# calculator3.net
KiCad netlist of a schematic drawn in EAGLE
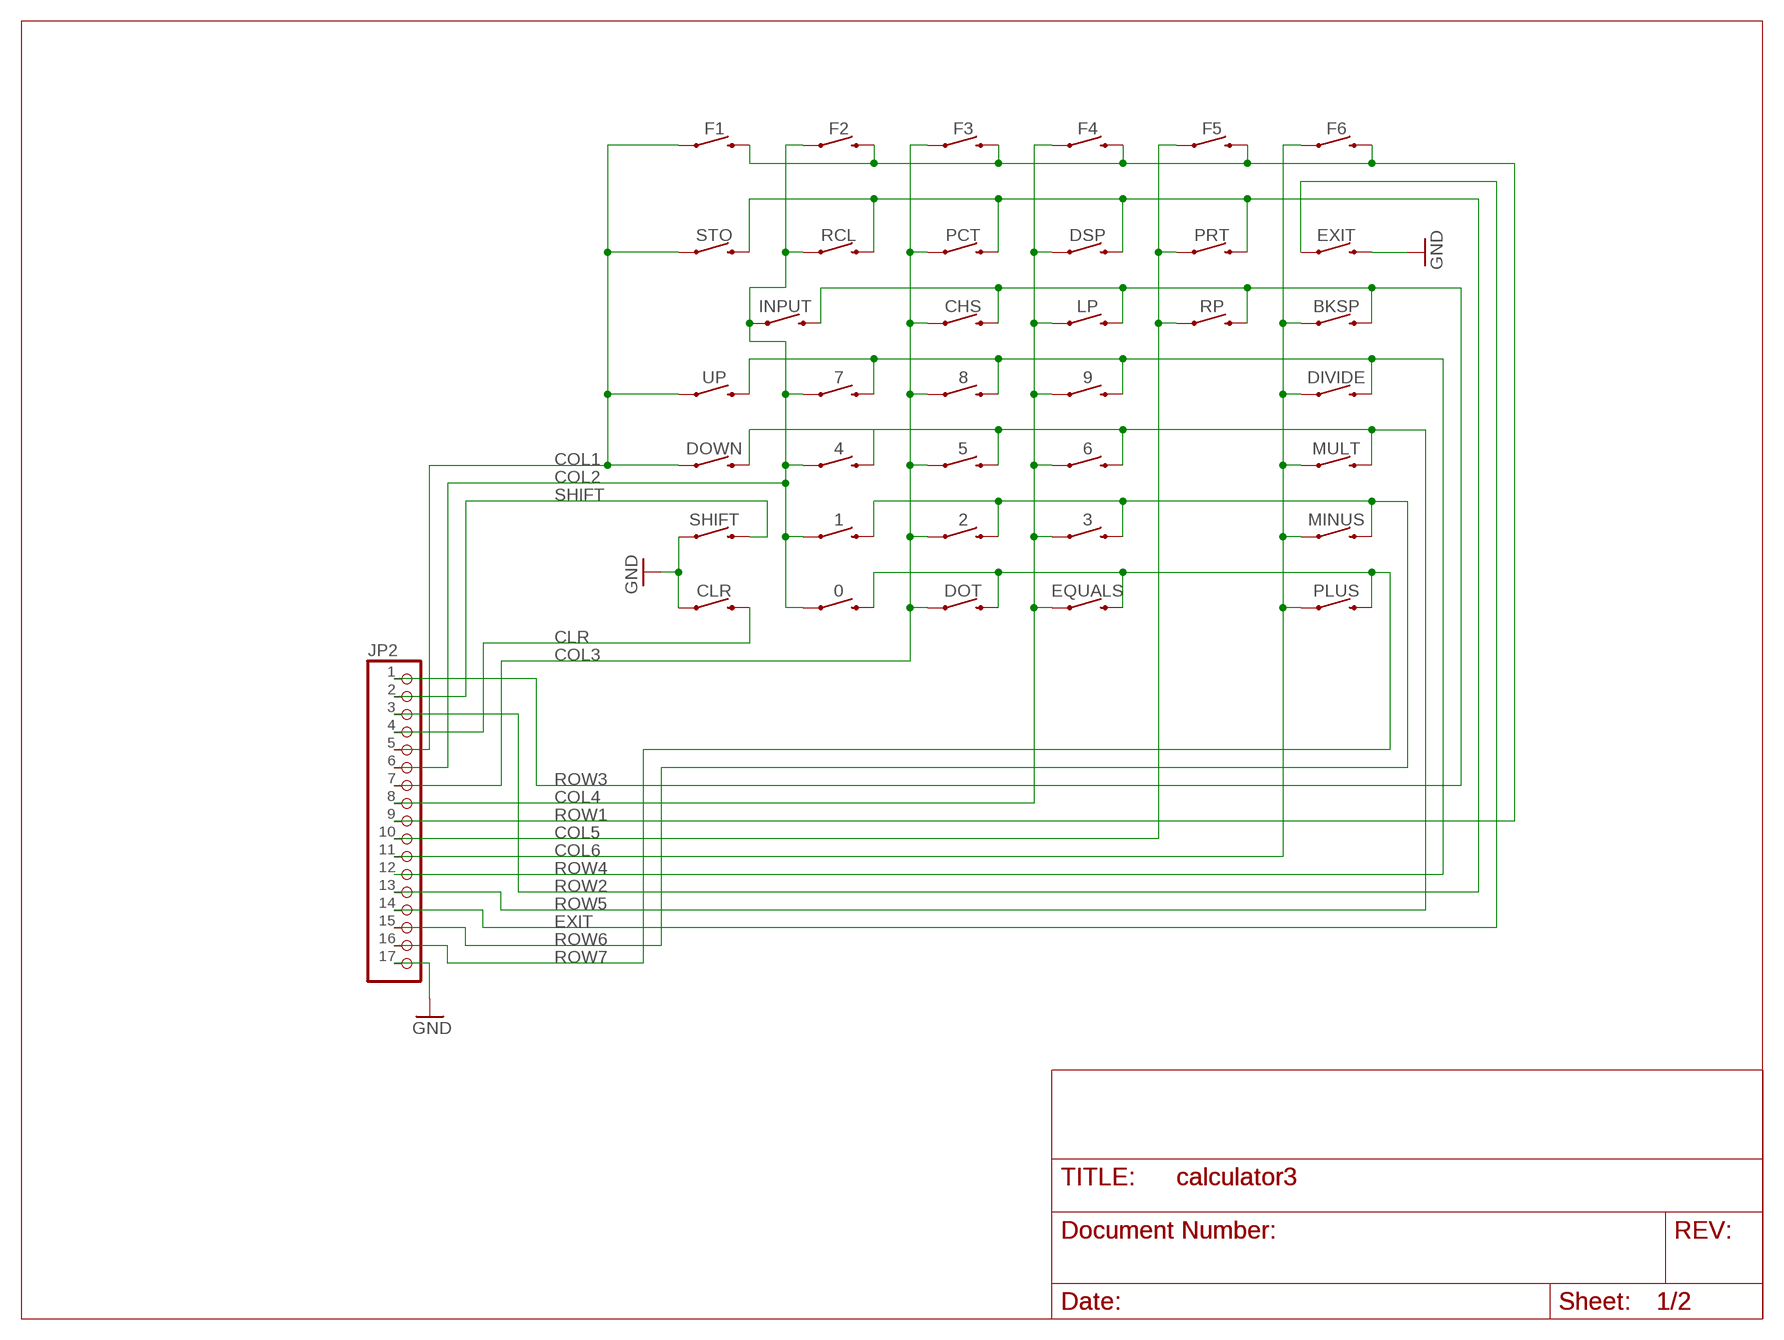
[diagram p0: schematic, sheet 1]
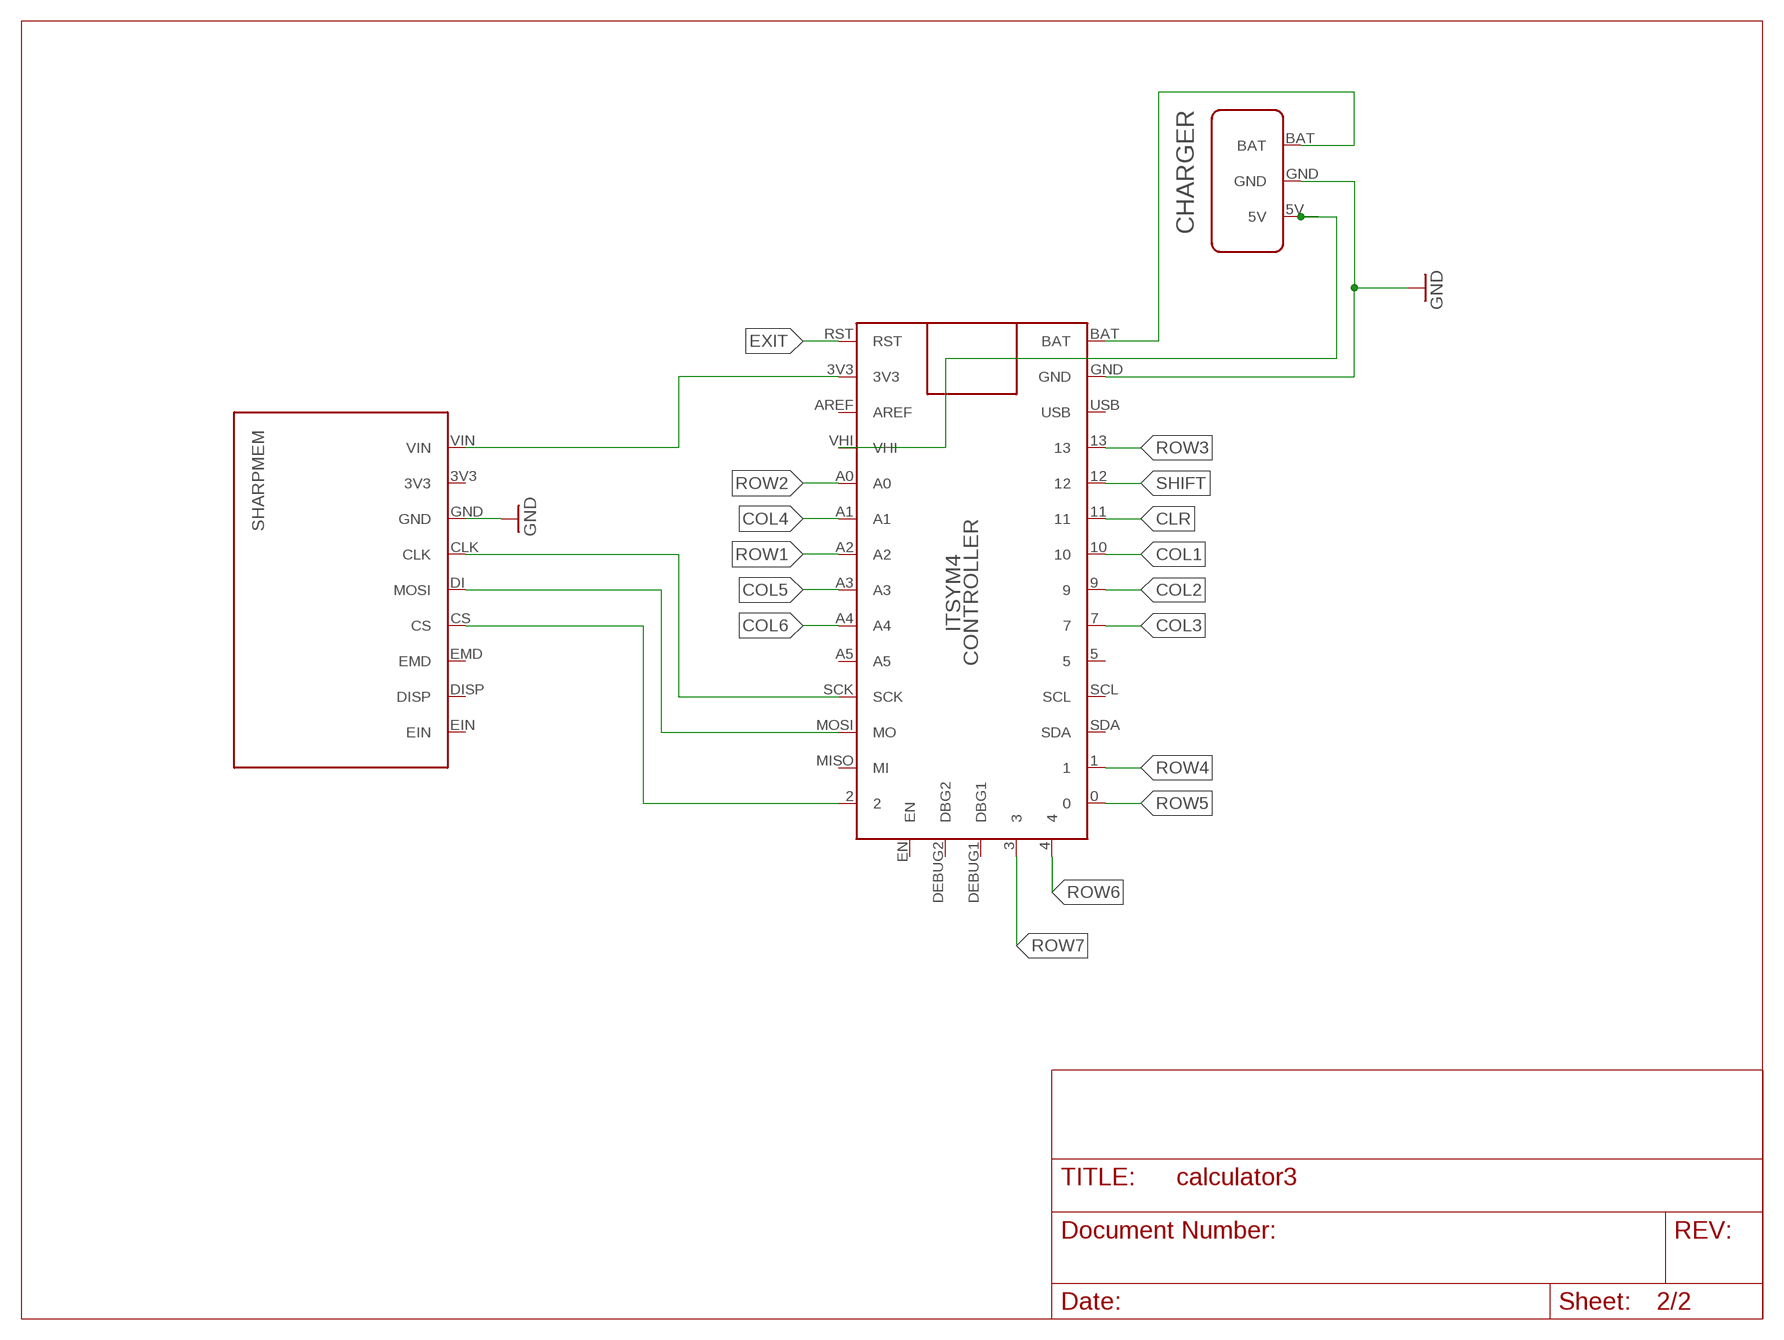
[diagram p1: schematic, sheet 2]

(export (version "E")
  (design (tool "Eeschema 10.0.6"))
  (components
    (comp (ref "0")
      (value "BUTTON")
      (footprint "eagle-import:BUTTON")
      (libsource (lib "eagle-import") (part "BUTTON"))
    )
    (comp (ref "1")
      (value "BUTTON")
      (footprint "eagle-import:BUTTON")
      (libsource (lib "eagle-import") (part "BUTTON"))
    )
    (comp (ref "2")
      (value "BUTTON")
      (footprint "eagle-import:BUTTON")
      (libsource (lib "eagle-import") (part "BUTTON"))
    )
    (comp (ref "3")
      (value "BUTTON")
      (footprint "eagle-import:BUTTON")
      (libsource (lib "eagle-import") (part "BUTTON"))
    )
    (comp (ref "4")
      (value "BUTTON")
      (footprint "eagle-import:BUTTON")
      (libsource (lib "eagle-import") (part "BUTTON"))
    )
    (comp (ref "5")
      (value "BUTTON")
      (footprint "eagle-import:BUTTON")
      (libsource (lib "eagle-import") (part "BUTTON"))
    )
    (comp (ref "6")
      (value "BUTTON")
      (footprint "eagle-import:BUTTON")
      (libsource (lib "eagle-import") (part "BUTTON"))
    )
    (comp (ref "7")
      (value "BUTTON")
      (footprint "eagle-import:BUTTON")
      (libsource (lib "eagle-import") (part "BUTTON"))
    )
    (comp (ref "8")
      (value "BUTTON")
      (footprint "eagle-import:BUTTON")
      (libsource (lib "eagle-import") (part "BUTTON"))
    )
    (comp (ref "9")
      (value "BUTTON")
      (footprint "eagle-import:BUTTON")
      (libsource (lib "eagle-import") (part "BUTTON"))
    )
    (comp (ref "BKSP")
      (value "BUTTON")
      (footprint "eagle-import:BUTTON")
      (libsource (lib "eagle-import") (part "BUTTON"))
    )
    (comp (ref "CHS")
      (value "BUTTON")
      (footprint "eagle-import:BUTTON")
      (libsource (lib "eagle-import") (part "BUTTON"))
    )
    (comp (ref "CLR")
      (value "BUTTON")
      (footprint "eagle-import:BUTTON")
      (libsource (lib "eagle-import") (part "BUTTON"))
    )
    (comp (ref "DIVIDE")
      (value "BUTTON")
      (footprint "eagle-import:BUTTON")
      (libsource (lib "eagle-import") (part "BUTTON"))
    )
    (comp (ref "DOT")
      (value "BUTTON")
      (footprint "eagle-import:BUTTON")
      (libsource (lib "eagle-import") (part "BUTTON"))
    )
    (comp (ref "DOWN")
      (value "BUTTON")
      (footprint "eagle-import:BUTTON")
      (libsource (lib "eagle-import") (part "BUTTON"))
    )
    (comp (ref "DSP")
      (value "BUTTON")
      (footprint "eagle-import:BUTTON")
      (libsource (lib "eagle-import") (part "BUTTON"))
    )
    (comp (ref "EQUALS")
      (value "BUTTON")
      (footprint "eagle-import:BUTTON")
      (libsource (lib "eagle-import") (part "BUTTON"))
    )
    (comp (ref "EXIT")
      (value "BUTTON")
      (footprint "eagle-import:BUTTON")
      (libsource (lib "eagle-import") (part "BUTTON"))
    )
    (comp (ref "F1")
      (value "BUTTON")
      (footprint "eagle-import:BUTTON")
      (libsource (lib "eagle-import") (part "BUTTON"))
    )
    (comp (ref "F2")
      (value "BUTTON")
      (footprint "eagle-import:BUTTON")
      (libsource (lib "eagle-import") (part "BUTTON"))
    )
    (comp (ref "F3")
      (value "BUTTON")
      (footprint "eagle-import:BUTTON")
      (libsource (lib "eagle-import") (part "BUTTON"))
    )
    (comp (ref "F4")
      (value "BUTTON")
      (footprint "eagle-import:BUTTON")
      (libsource (lib "eagle-import") (part "BUTTON"))
    )
    (comp (ref "F5")
      (value "BUTTON")
      (footprint "eagle-import:BUTTON")
      (libsource (lib "eagle-import") (part "BUTTON"))
    )
    (comp (ref "F6")
      (value "BUTTON")
      (footprint "eagle-import:BUTTON")
      (libsource (lib "eagle-import") (part "BUTTON"))
    )
    (comp (ref "INPUT")
      (value "BUTTON")
      (footprint "eagle-import:BUTTON")
      (libsource (lib "eagle-import") (part "BUTTON"))
    )
    (comp (ref "JP2")
      (value "PINHD-1X17/90")
      (footprint "eagle-import:1X17_90")
      (libsource (lib "eagle-import") (part "PINHD-1X17/90"))
    )
    (comp (ref "LP")
      (value "BUTTON")
      (footprint "eagle-import:BUTTON")
      (libsource (lib "eagle-import") (part "BUTTON"))
    )
    (comp (ref "MINUS")
      (value "BUTTON")
      (footprint "eagle-import:BUTTON")
      (libsource (lib "eagle-import") (part "BUTTON"))
    )
    (comp (ref "MULT")
      (value "BUTTON")
      (footprint "eagle-import:BUTTON")
      (libsource (lib "eagle-import") (part "BUTTON"))
    )
    (comp (ref "PCT")
      (value "BUTTON")
      (footprint "eagle-import:BUTTON")
      (libsource (lib "eagle-import") (part "BUTTON"))
    )
    (comp (ref "PLUS")
      (value "BUTTON")
      (footprint "eagle-import:BUTTON")
      (libsource (lib "eagle-import") (part "BUTTON"))
    )
    (comp (ref "PRT")
      (value "BUTTON")
      (footprint "eagle-import:BUTTON")
      (libsource (lib "eagle-import") (part "BUTTON"))
    )
    (comp (ref "RCL")
      (value "BUTTON")
      (footprint "eagle-import:BUTTON")
      (libsource (lib "eagle-import") (part "BUTTON"))
    )
    (comp (ref "RP")
      (value "BUTTON")
      (footprint "eagle-import:BUTTON")
      (libsource (lib "eagle-import") (part "BUTTON"))
    )
    (comp (ref "SHIFT")
      (value "BUTTON")
      (footprint "eagle-import:BUTTON")
      (libsource (lib "eagle-import") (part "BUTTON"))
    )
    (comp (ref "STO")
      (value "BUTTON")
      (footprint "eagle-import:BUTTON")
      (libsource (lib "eagle-import") (part "BUTTON"))
    )
    (comp (ref "UP")
      (value "BUTTON")
      (footprint "eagle-import:BUTTON")
      (libsource (lib "eagle-import") (part "BUTTON"))
    )
    (comp (ref "CHARGER")
      (value "LIPO_BACKPACK")
      (footprint "eagle-import:LIPO_BACKPACK")
      (libsource (lib "eagle-import") (part "LIPO_BACKPACK"))
    )
    (comp (ref "CONTROLLER")
      (value "ITSYM4")
      (footprint "eagle-import:ITSYM4")
      (libsource (lib "eagle-import") (part "ITSYM4"))
    )
    (comp (ref "SHARPMEM")
      (value "SHARPMEM")
      (footprint "eagle-import:SHARPMEM")
      (libsource (lib "eagle-import") (part "SHARPMEM"))
    )
  )
  (nets
    (net (code "1") (name "CLR") (class "Default")
      (node (ref "CLR") (pin "3") (pinfunction "2_3") (pintype "passive"))
      (node (ref "CONTROLLER") (pin "11") (pinfunction "11_11") (pintype "bidirectional"))
      (node (ref "JP2") (pin "4") (pinfunction "4_4") (pintype "passive"))
    )
    (net (code "2") (name "COL1") (class "Default")
      (node (ref "CONTROLLER") (pin "10") (pinfunction "10_10") (pintype "bidirectional"))
      (node (ref "DOWN") (pin "1") (pinfunction "1_1") (pintype "passive"))
      (node (ref "F1") (pin "1") (pinfunction "1_1") (pintype "passive"))
      (node (ref "JP2") (pin "5") (pinfunction "5_5") (pintype "passive"))
      (node (ref "STO") (pin "1") (pinfunction "1_1") (pintype "passive"))
      (node (ref "UP") (pin "1") (pinfunction "1_1") (pintype "passive"))
    )
    (net (code "3") (name "COL2") (class "Default")
      (node (ref "0") (pin "1") (pinfunction "1_1") (pintype "passive"))
      (node (ref "1") (pin "1") (pinfunction "1_1") (pintype "passive"))
      (node (ref "4") (pin "1") (pinfunction "1_1") (pintype "passive"))
      (node (ref "7") (pin "1") (pinfunction "1_1") (pintype "passive"))
      (node (ref "CONTROLLER") (pin "9") (pinfunction "9_9") (pintype "bidirectional"))
      (node (ref "F2") (pin "1") (pinfunction "1_1") (pintype "passive"))
      (node (ref "INPUT") (pin "1") (pinfunction "1_1") (pintype "passive"))
      (node (ref "JP2") (pin "6") (pinfunction "6_6") (pintype "passive"))
      (node (ref "RCL") (pin "1") (pinfunction "1_1") (pintype "passive"))
    )
    (net (code "4") (name "COL3") (class "Default")
      (node (ref "2") (pin "1") (pinfunction "1_1") (pintype "passive"))
      (node (ref "5") (pin "1") (pinfunction "1_1") (pintype "passive"))
      (node (ref "8") (pin "1") (pinfunction "1_1") (pintype "passive"))
      (node (ref "CHS") (pin "1") (pinfunction "1_1") (pintype "passive"))
      (node (ref "CONTROLLER") (pin "7") (pinfunction "7_7") (pintype "bidirectional"))
      (node (ref "DOT") (pin "1") (pinfunction "1_1") (pintype "passive"))
      (node (ref "F3") (pin "1") (pinfunction "1_1") (pintype "passive"))
      (node (ref "JP2") (pin "7") (pinfunction "7_7") (pintype "passive"))
      (node (ref "PCT") (pin "1") (pinfunction "1_1") (pintype "passive"))
    )
    (net (code "5") (name "COL4") (class "Default")
      (node (ref "3") (pin "1") (pinfunction "1_1") (pintype "passive"))
      (node (ref "6") (pin "1") (pinfunction "1_1") (pintype "passive"))
      (node (ref "9") (pin "1") (pinfunction "1_1") (pintype "passive"))
      (node (ref "CONTROLLER") (pin "A1") (pinfunction "A1_A1") (pintype "bidirectional"))
      (node (ref "DSP") (pin "1") (pinfunction "1_1") (pintype "passive"))
      (node (ref "EQUALS") (pin "1") (pinfunction "1_1") (pintype "passive"))
      (node (ref "F4") (pin "1") (pinfunction "1_1") (pintype "passive"))
      (node (ref "JP2") (pin "8") (pinfunction "8_8") (pintype "passive"))
      (node (ref "LP") (pin "1") (pinfunction "1_1") (pintype "passive"))
    )
    (net (code "6") (name "COL5") (class "Default")
      (node (ref "CONTROLLER") (pin "A3") (pinfunction "A3_A3") (pintype "bidirectional"))
      (node (ref "F5") (pin "1") (pinfunction "1_1") (pintype "passive"))
      (node (ref "JP2") (pin "10") (pinfunction "10_10") (pintype "passive"))
      (node (ref "PRT") (pin "1") (pinfunction "1_1") (pintype "passive"))
      (node (ref "RP") (pin "1") (pinfunction "1_1") (pintype "passive"))
    )
    (net (code "7") (name "COL6") (class "Default")
      (node (ref "BKSP") (pin "1") (pinfunction "1_1") (pintype "passive"))
      (node (ref "CONTROLLER") (pin "A4") (pinfunction "A4_A4") (pintype "bidirectional"))
      (node (ref "DIVIDE") (pin "1") (pinfunction "1_1") (pintype "passive"))
      (node (ref "F6") (pin "1") (pinfunction "1_1") (pintype "passive"))
      (node (ref "JP2") (pin "11") (pinfunction "11_11") (pintype "passive"))
      (node (ref "MINUS") (pin "1") (pinfunction "1_1") (pintype "passive"))
      (node (ref "MULT") (pin "1") (pinfunction "1_1") (pintype "passive"))
      (node (ref "PLUS") (pin "1") (pinfunction "1_1") (pintype "passive"))
    )
    (net (code "8") (name "EXIT") (class "Default")
      (node (ref "CONTROLLER") (pin "RST") (pinfunction "RST_RST") (pintype "bidirectional"))
      (node (ref "EXIT") (pin "1") (pinfunction "1_1") (pintype "passive"))
      (node (ref "JP2") (pin "14") (pinfunction "14_14") (pintype "passive"))
    )
    (net (code "9") (name "GND") (class "Default")
      (node (ref "CHARGER") (pin "GND") (pinfunction "GND_GND") (pintype "bidirectional"))
      (node (ref "CLR") (pin "1") (pinfunction "1_1") (pintype "passive"))
      (node (ref "CONTROLLER") (pin "GND") (pinfunction "GND_GND") (pintype "bidirectional"))
      (node (ref "EXIT") (pin "3") (pinfunction "2_3") (pintype "passive"))
      (node (ref "JP2") (pin "17") (pinfunction "17_17") (pintype "passive"))
      (node (ref "SHARPMEM") (pin "GND") (pinfunction "GND_GND") (pintype "bidirectional"))
      (node (ref "SHIFT") (pin "1") (pinfunction "1_1") (pintype "passive"))
    )
    (net (code "10") (name "Net-(CHARGER-Pad5V)") (class "Default")
      (node (ref "CHARGER") (pin "5V") (pinfunction "5V_5V") (pintype "bidirectional"))
      (node (ref "CONTROLLER") (pin "VHI") (pinfunction "VHI_VHI") (pintype "bidirectional"))
    )
    (net (code "11") (name "Net-(CHARGER-PadBAT)") (class "Default")
      (node (ref "CHARGER") (pin "BAT") (pinfunction "BAT_BAT") (pintype "bidirectional"))
      (node (ref "CONTROLLER") (pin "BAT") (pinfunction "BAT_BAT") (pintype "bidirectional"))
    )
    (net (code "12") (name "Net-(CONTROLLER-MO)") (class "Default")
      (node (ref "CONTROLLER") (pin "MOSI") (pinfunction "MO_MOSI") (pintype "bidirectional"))
      (node (ref "SHARPMEM") (pin "DI") (pinfunction "MOSI_DI") (pintype "bidirectional"))
    )
    (net (code "13") (name "Net-(CONTROLLER-Pad2)") (class "Default")
      (node (ref "CONTROLLER") (pin "2") (pinfunction "2_2") (pintype "bidirectional"))
      (node (ref "SHARPMEM") (pin "CS") (pinfunction "CS_CS") (pintype "bidirectional"))
    )
    (net (code "14") (name "Net-(CONTROLLER-Pad3V3)") (class "Default")
      (node (ref "CONTROLLER") (pin "3V3") (pinfunction "3V3_3V3") (pintype "bidirectional"))
      (node (ref "SHARPMEM") (pin "VIN") (pinfunction "VIN_VIN") (pintype "bidirectional"))
    )
    (net (code "15") (name "Net-(CONTROLLER-PadSCK)") (class "Default")
      (node (ref "CONTROLLER") (pin "SCK") (pinfunction "SCK_SCK") (pintype "bidirectional"))
      (node (ref "SHARPMEM") (pin "CLK") (pinfunction "CLK_CLK") (pintype "bidirectional"))
    )
    (net (code "16") (name "ROW1") (class "Default")
      (node (ref "CONTROLLER") (pin "A2") (pinfunction "A2_A2") (pintype "bidirectional"))
      (node (ref "F1") (pin "3") (pinfunction "2_3") (pintype "passive"))
      (node (ref "F2") (pin "3") (pinfunction "2_3") (pintype "passive"))
      (node (ref "F3") (pin "3") (pinfunction "2_3") (pintype "passive"))
      (node (ref "F4") (pin "3") (pinfunction "2_3") (pintype "passive"))
      (node (ref "F5") (pin "3") (pinfunction "2_3") (pintype "passive"))
      (node (ref "F6") (pin "3") (pinfunction "2_3") (pintype "passive"))
      (node (ref "JP2") (pin "9") (pinfunction "9_9") (pintype "passive"))
    )
    (net (code "17") (name "ROW2") (class "Default")
      (node (ref "CONTROLLER") (pin "A0") (pinfunction "A0_A0") (pintype "bidirectional"))
      (node (ref "DSP") (pin "3") (pinfunction "2_3") (pintype "passive"))
      (node (ref "JP2") (pin "3") (pinfunction "3_3") (pintype "passive"))
      (node (ref "PCT") (pin "3") (pinfunction "2_3") (pintype "passive"))
      (node (ref "PRT") (pin "3") (pinfunction "2_3") (pintype "passive"))
      (node (ref "RCL") (pin "3") (pinfunction "2_3") (pintype "passive"))
      (node (ref "STO") (pin "3") (pinfunction "2_3") (pintype "passive"))
    )
    (net (code "18") (name "ROW3") (class "Default")
      (node (ref "BKSP") (pin "3") (pinfunction "2_3") (pintype "passive"))
      (node (ref "CHS") (pin "3") (pinfunction "2_3") (pintype "passive"))
      (node (ref "CONTROLLER") (pin "13") (pinfunction "13_13") (pintype "bidirectional"))
      (node (ref "INPUT") (pin "3") (pinfunction "2_3") (pintype "passive"))
      (node (ref "JP2") (pin "1") (pinfunction "1_1") (pintype "passive"))
      (node (ref "LP") (pin "3") (pinfunction "2_3") (pintype "passive"))
      (node (ref "RP") (pin "3") (pinfunction "2_3") (pintype "passive"))
    )
    (net (code "19") (name "ROW4") (class "Default")
      (node (ref "7") (pin "3") (pinfunction "2_3") (pintype "passive"))
      (node (ref "8") (pin "3") (pinfunction "2_3") (pintype "passive"))
      (node (ref "9") (pin "3") (pinfunction "2_3") (pintype "passive"))
      (node (ref "CONTROLLER") (pin "1") (pinfunction "1_1") (pintype "bidirectional"))
      (node (ref "DIVIDE") (pin "3") (pinfunction "2_3") (pintype "passive"))
      (node (ref "JP2") (pin "12") (pinfunction "12_12") (pintype "passive"))
      (node (ref "UP") (pin "3") (pinfunction "2_3") (pintype "passive"))
    )
    (net (code "20") (name "ROW5") (class "Default")
      (node (ref "4") (pin "3") (pinfunction "2_3") (pintype "passive"))
      (node (ref "5") (pin "3") (pinfunction "2_3") (pintype "passive"))
      (node (ref "6") (pin "3") (pinfunction "2_3") (pintype "passive"))
      (node (ref "CONTROLLER") (pin "0") (pinfunction "0_0") (pintype "bidirectional"))
      (node (ref "DOWN") (pin "3") (pinfunction "2_3") (pintype "passive"))
      (node (ref "JP2") (pin "13") (pinfunction "13_13") (pintype "passive"))
      (node (ref "MULT") (pin "3") (pinfunction "2_3") (pintype "passive"))
    )
    (net (code "21") (name "ROW6") (class "Default")
      (node (ref "1") (pin "3") (pinfunction "2_3") (pintype "passive"))
      (node (ref "2") (pin "3") (pinfunction "2_3") (pintype "passive"))
      (node (ref "3") (pin "3") (pinfunction "2_3") (pintype "passive"))
      (node (ref "CONTROLLER") (pin "4") (pinfunction "4_4") (pintype "bidirectional"))
      (node (ref "JP2") (pin "15") (pinfunction "15_15") (pintype "passive"))
      (node (ref "MINUS") (pin "3") (pinfunction "2_3") (pintype "passive"))
    )
    (net (code "22") (name "ROW7") (class "Default")
      (node (ref "0") (pin "3") (pinfunction "2_3") (pintype "passive"))
      (node (ref "CONTROLLER") (pin "3") (pinfunction "3_3") (pintype "bidirectional"))
      (node (ref "DOT") (pin "3") (pinfunction "2_3") (pintype "passive"))
      (node (ref "EQUALS") (pin "3") (pinfunction "2_3") (pintype "passive"))
      (node (ref "JP2") (pin "16") (pinfunction "16_16") (pintype "passive"))
      (node (ref "PLUS") (pin "3") (pinfunction "2_3") (pintype "passive"))
    )
    (net (code "23") (name "SHIFT") (class "Default")
      (node (ref "CONTROLLER") (pin "12") (pinfunction "12_12") (pintype "bidirectional"))
      (node (ref "JP2") (pin "2") (pinfunction "2_2") (pintype "passive"))
      (node (ref "SHIFT") (pin "3") (pinfunction "2_3") (pintype "passive"))
    )
    (net (code "24") (name "unconnected-(CONTROLLER-DBG1-PadDEBUG1)") (class "Default")
      (node (ref "CONTROLLER") (pin "DEBUG1") (pinfunction "DBG1_DEBUG1") (pintype "bidirectional"))
    )
    (net (code "25") (name "unconnected-(CONTROLLER-DBG2-PadDEBUG2)") (class "Default")
      (node (ref "CONTROLLER") (pin "DEBUG2") (pinfunction "DBG2_DEBUG2") (pintype "bidirectional"))
    )
    (net (code "26") (name "unconnected-(CONTROLLER-MI-PadMISO)") (class "Default")
      (node (ref "CONTROLLER") (pin "MISO") (pinfunction "MI_MISO") (pintype "bidirectional"))
    )
    (net (code "27") (name "unconnected-(CONTROLLER-Pad5)") (class "Default")
      (node (ref "CONTROLLER") (pin "5") (pinfunction "5_5") (pintype "bidirectional"))
    )
    (net (code "28") (name "unconnected-(CONTROLLER-PadA5)") (class "Default")
      (node (ref "CONTROLLER") (pin "A5") (pinfunction "A5_A5") (pintype "bidirectional"))
    )
    (net (code "29") (name "unconnected-(CONTROLLER-PadAREF)") (class "Default")
      (node (ref "CONTROLLER") (pin "AREF") (pinfunction "AREF_AREF") (pintype "bidirectional"))
    )
    (net (code "30") (name "unconnected-(CONTROLLER-PadEN)") (class "Default")
      (node (ref "CONTROLLER") (pin "EN") (pinfunction "EN_EN") (pintype "bidirectional"))
    )
    (net (code "31") (name "unconnected-(CONTROLLER-PadSCL)") (class "Default")
      (node (ref "CONTROLLER") (pin "SCL") (pinfunction "SCL_SCL") (pintype "bidirectional"))
    )
    (net (code "32") (name "unconnected-(CONTROLLER-PadSDA)") (class "Default")
      (node (ref "CONTROLLER") (pin "SDA") (pinfunction "SDA_SDA") (pintype "bidirectional"))
    )
    (net (code "33") (name "unconnected-(CONTROLLER-PadUSB)") (class "Default")
      (node (ref "CONTROLLER") (pin "USB") (pinfunction "USB_USB") (pintype "bidirectional"))
    )
    (net (code "34") (name "unconnected-(SHARPMEM-Pad3V3)") (class "Default")
      (node (ref "SHARPMEM") (pin "3V3") (pinfunction "3V3_3V3") (pintype "bidirectional"))
    )
    (net (code "35") (name "unconnected-(SHARPMEM-PadDISP)") (class "Default")
      (node (ref "SHARPMEM") (pin "DISP") (pinfunction "DISP_DISP") (pintype "bidirectional"))
    )
    (net (code "36") (name "unconnected-(SHARPMEM-PadEIN)") (class "Default")
      (node (ref "SHARPMEM") (pin "EIN") (pinfunction "EIN_EIN") (pintype "bidirectional"))
    )
    (net (code "37") (name "unconnected-(SHARPMEM-PadEMD)") (class "Default")
      (node (ref "SHARPMEM") (pin "EMD") (pinfunction "EMD_EMD") (pintype "bidirectional"))
    )
  )
)
